# MotionSensorModule.net
KiCad netlist of a schematic drawn in EAGLE
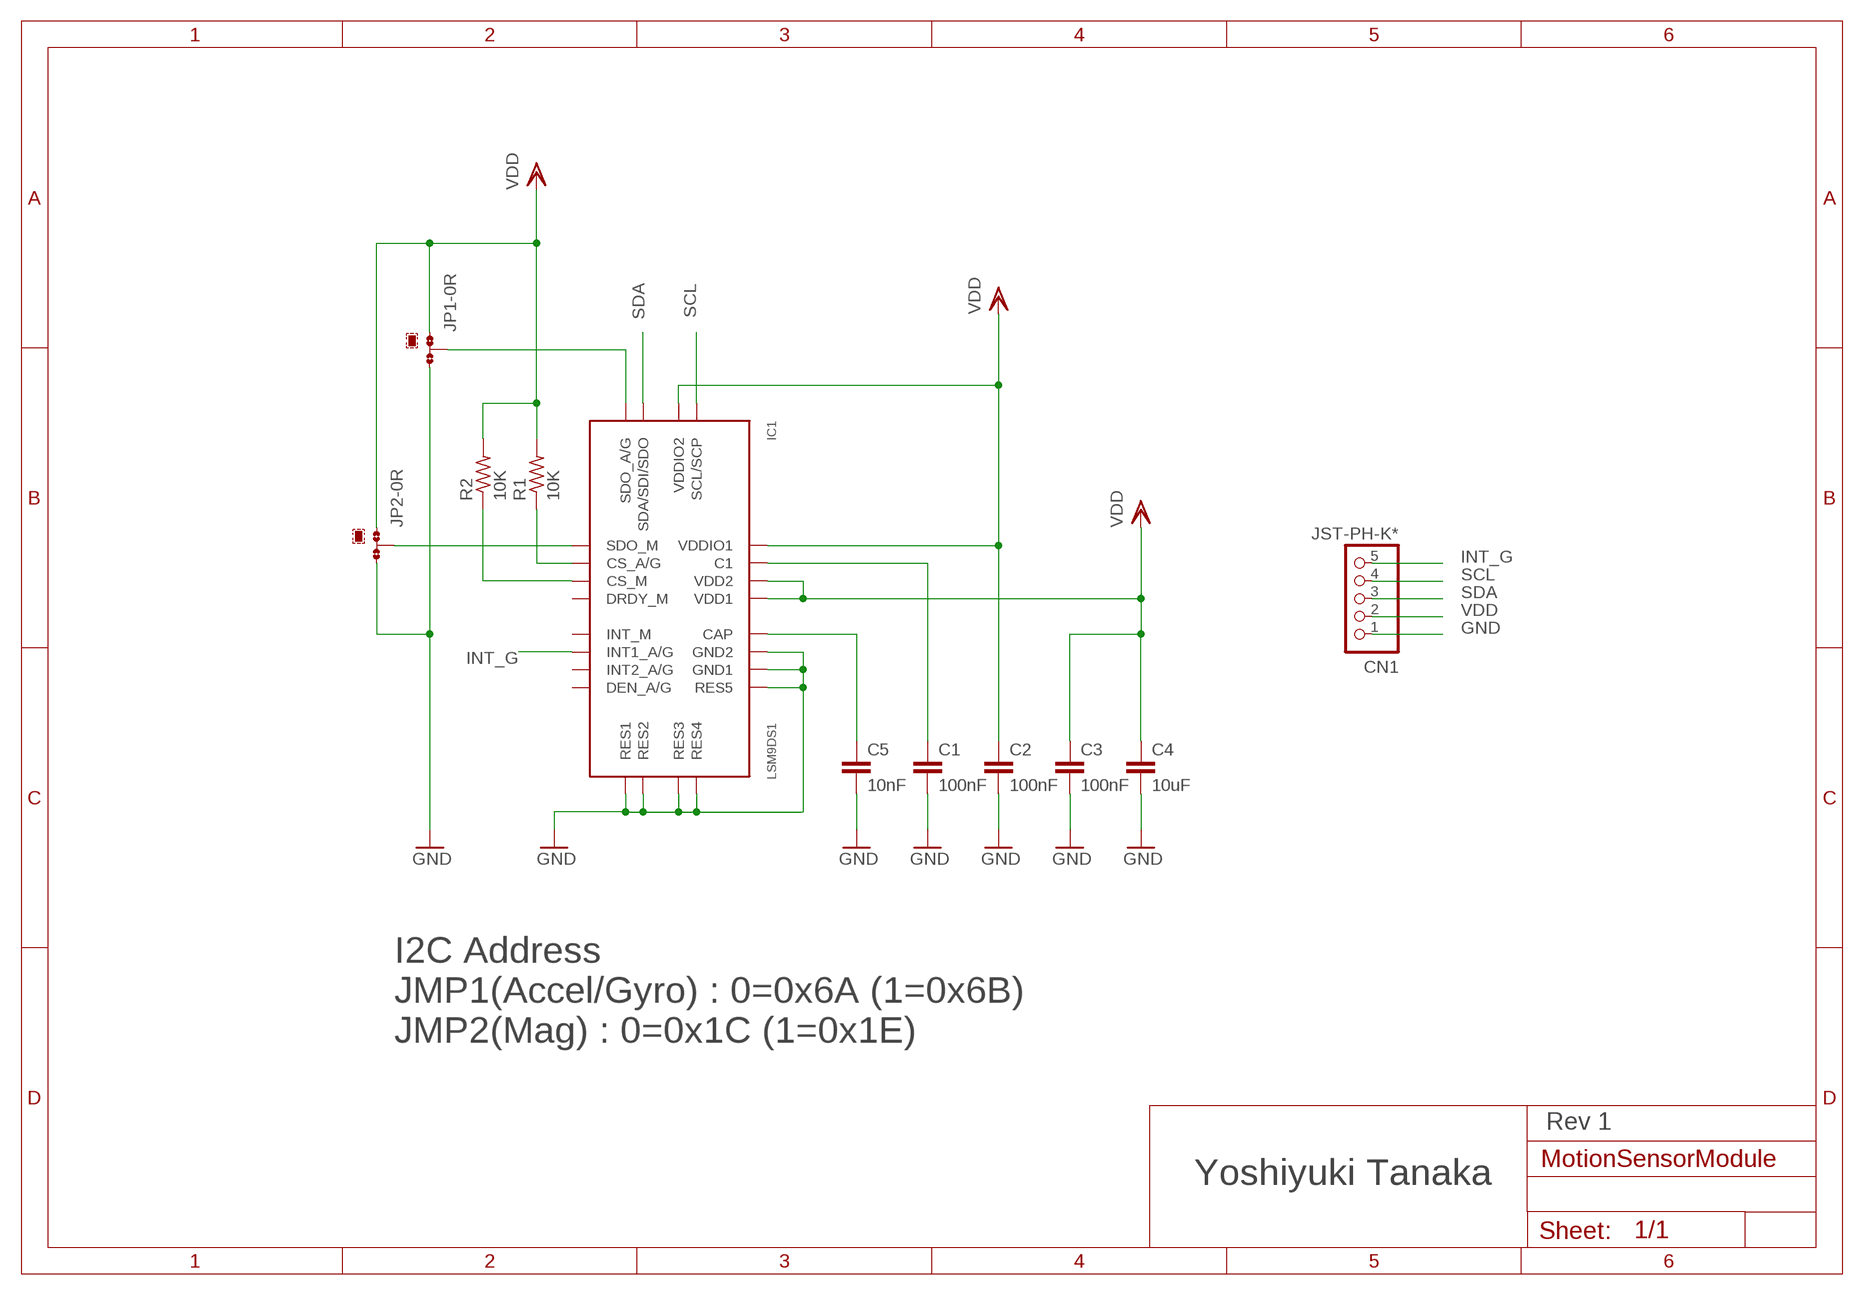
[diagram p0: schematic, sheet 1]

(export (version "E")
  (design (tool "Eeschema 10.0.6"))
  (components
    (comp (ref "C1")
      (value "100nF")
      (footprint "eagle-import:C0603")
      (libsource (lib "eagle-import") (part "C-EUC0603"))
    )
    (comp (ref "C2")
      (value "100nF")
      (footprint "eagle-import:C0603")
      (libsource (lib "eagle-import") (part "C-EUC0603"))
    )
    (comp (ref "C3")
      (value "100nF")
      (footprint "eagle-import:C0603")
      (libsource (lib "eagle-import") (part "C-EUC0603"))
    )
    (comp (ref "C4")
      (value "10uF")
      (footprint "eagle-import:C0603")
      (libsource (lib "eagle-import") (part "C-EUC0603"))
    )
    (comp (ref "C5")
      (value "10nF")
      (footprint "eagle-import:C0603")
      (libsource (lib "eagle-import") (part "C-EUC0603"))
    )
    (comp (ref "CN1")
      (value "JST-PH-K*")
      (footprint "eagle-import:B5B-PH-SM4-TB")
      (libsource (lib "eagle-import") (part "B5B-PH-SM4-TB"))
    )
    (comp (ref "IC1")
      (value "LSM9DS1")
      (footprint "eagle-import:LGA-24L")
      (libsource (lib "eagle-import") (part "LSM9DS1"))
    )
    (comp (ref "JP1")
      (value "0R-JUMPB")
      (footprint "eagle-import:B0R-JMP")
      (libsource (lib "eagle-import") (part "0R-JUMPB"))
    )
    (comp (ref "JP2")
      (value "0R-JUMPB")
      (footprint "eagle-import:B0R-JMP")
      (libsource (lib "eagle-import") (part "0R-JUMPB"))
    )
    (comp (ref "R1")
      (value "10K")
      (footprint "eagle-import:R0603")
      (libsource (lib "eagle-import") (part "R-US_R0603"))
    )
    (comp (ref "R2")
      (value "10K")
      (footprint "eagle-import:R0603")
      (libsource (lib "eagle-import") (part "R-US_R0603"))
    )
  )
  (nets
    (net (code "1") (name "/INT_G") (class "Default")
      (node (ref "CN1") (pin "5") (pinfunction "5_5") (pintype "passive"))
      (node (ref "IC1") (pin "11") (pinfunction "INT1_A/G_11") (pintype "bidirectional"))
    )
    (net (code "2") (name "/SCL") (class "Default")
      (node (ref "CN1") (pin "4") (pinfunction "4_4") (pintype "passive"))
      (node (ref "IC1") (pin "2") (pinfunction "SCL/SCP_2") (pintype "bidirectional"))
    )
    (net (code "3") (name "/SDA") (class "Default")
      (node (ref "CN1") (pin "3") (pinfunction "3_3") (pintype "passive"))
      (node (ref "IC1") (pin "4") (pinfunction "SDA/SDI/SDO_4") (pintype "bidirectional"))
    )
    (net (code "4") (name "GND") (class "Default")
      (node (ref "C1") (pin "2") (pinfunction "2_2") (pintype "passive"))
      (node (ref "C2") (pin "2") (pinfunction "2_2") (pintype "passive"))
      (node (ref "C3") (pin "2") (pinfunction "2_2") (pintype "passive"))
      (node (ref "C4") (pin "2") (pinfunction "2_2") (pintype "passive"))
      (node (ref "C5") (pin "2") (pinfunction "2_2") (pintype "passive"))
      (node (ref "CN1") (pin "1") (pinfunction "1_1") (pintype "passive"))
      (node (ref "IC1") (pin "14") (pinfunction "RES1_14") (pintype "bidirectional"))
      (node (ref "IC1") (pin "15") (pinfunction "RES2_15") (pintype "bidirectional"))
      (node (ref "IC1") (pin "16") (pinfunction "RES3_16") (pintype "bidirectional"))
      (node (ref "IC1") (pin "17") (pinfunction "RES4_17") (pintype "bidirectional"))
      (node (ref "IC1") (pin "18") (pinfunction "RES5_18") (pintype "bidirectional"))
      (node (ref "IC1") (pin "19") (pinfunction "GND1_19") (pintype "power_in"))
      (node (ref "IC1") (pin "20") (pinfunction "GND2_20") (pintype "power_in"))
      (node (ref "JP1") (pin "3") (pinfunction "3_3") (pintype "passive"))
      (node (ref "JP2") (pin "3") (pinfunction "3_3") (pintype "passive"))
    )
    (net (code "5") (name "Net-(IC1-C1)") (class "Default")
      (node (ref "C1") (pin "1") (pinfunction "1_1") (pintype "passive"))
      (node (ref "IC1") (pin "24") (pinfunction "C1_24") (pintype "power_in"))
    )
    (net (code "6") (name "Net-(IC1-CAP)") (class "Default")
      (node (ref "C5") (pin "1") (pinfunction "1_1") (pintype "passive"))
      (node (ref "IC1") (pin "21") (pinfunction "CAP_21") (pintype "power_in"))
    )
    (net (code "7") (name "Net-(IC1-CS_A{slash}G)") (class "Default")
      (node (ref "IC1") (pin "7") (pinfunction "CS_A/G_7") (pintype "bidirectional"))
      (node (ref "R1") (pin "1") (pinfunction "1_1") (pintype "passive"))
    )
    (net (code "8") (name "Net-(IC1-CS_M)") (class "Default")
      (node (ref "IC1") (pin "8") (pinfunction "CS_M_8") (pintype "bidirectional"))
      (node (ref "R2") (pin "1") (pinfunction "1_1") (pintype "passive"))
    )
    (net (code "9") (name "Net-(IC1-SDO_A{slash}G)") (class "Default")
      (node (ref "IC1") (pin "5") (pinfunction "SDO_A/G_5") (pintype "bidirectional"))
      (node (ref "JP1") (pin "2") (pinfunction "2_2") (pintype "passive"))
    )
    (net (code "10") (name "Net-(IC1-SDO_M)") (class "Default")
      (node (ref "IC1") (pin "6") (pinfunction "SDO_M_6") (pintype "bidirectional"))
      (node (ref "JP2") (pin "2") (pinfunction "2_2") (pintype "passive"))
    )
    (net (code "11") (name "VDD") (class "Default")
      (node (ref "C2") (pin "1") (pinfunction "1_1") (pintype "passive"))
      (node (ref "C3") (pin "1") (pinfunction "1_1") (pintype "passive"))
      (node (ref "C4") (pin "1") (pinfunction "1_1") (pintype "passive"))
      (node (ref "CN1") (pin "2") (pinfunction "2_2") (pintype "passive"))
      (node (ref "IC1") (pin "1") (pinfunction "VDDIO1_1") (pintype "power_in"))
      (node (ref "IC1") (pin "22") (pinfunction "VDD1_22") (pintype "power_in"))
      (node (ref "IC1") (pin "23") (pinfunction "VDD2_23") (pintype "power_in"))
      (node (ref "IC1") (pin "3") (pinfunction "VDDIO2_3") (pintype "power_in"))
      (node (ref "JP1") (pin "1") (pinfunction "1_1") (pintype "passive"))
      (node (ref "JP2") (pin "1") (pinfunction "1_1") (pintype "passive"))
      (node (ref "R1") (pin "2") (pinfunction "2_2") (pintype "passive"))
      (node (ref "R2") (pin "2") (pinfunction "2_2") (pintype "passive"))
    )
    (net (code "12") (name "unconnected-(IC1-DEN_A{slash}G-Pad13)") (class "Default")
      (node (ref "IC1") (pin "13") (pinfunction "DEN_A/G_13") (pintype "bidirectional"))
    )
    (net (code "13") (name "unconnected-(IC1-DRDY_M-Pad9)") (class "Default")
      (node (ref "IC1") (pin "9") (pinfunction "DRDY_M_9") (pintype "bidirectional"))
    )
    (net (code "14") (name "unconnected-(IC1-INT2_A{slash}G-Pad12)") (class "Default")
      (node (ref "IC1") (pin "12") (pinfunction "INT2_A/G_12") (pintype "bidirectional"))
    )
    (net (code "15") (name "unconnected-(IC1-INT_M-Pad10)") (class "Default")
      (node (ref "IC1") (pin "10") (pinfunction "INT_M_10") (pintype "bidirectional"))
    )
  )
)
